# synth.net
KiCad netlist of a schematic drawn in EAGLE
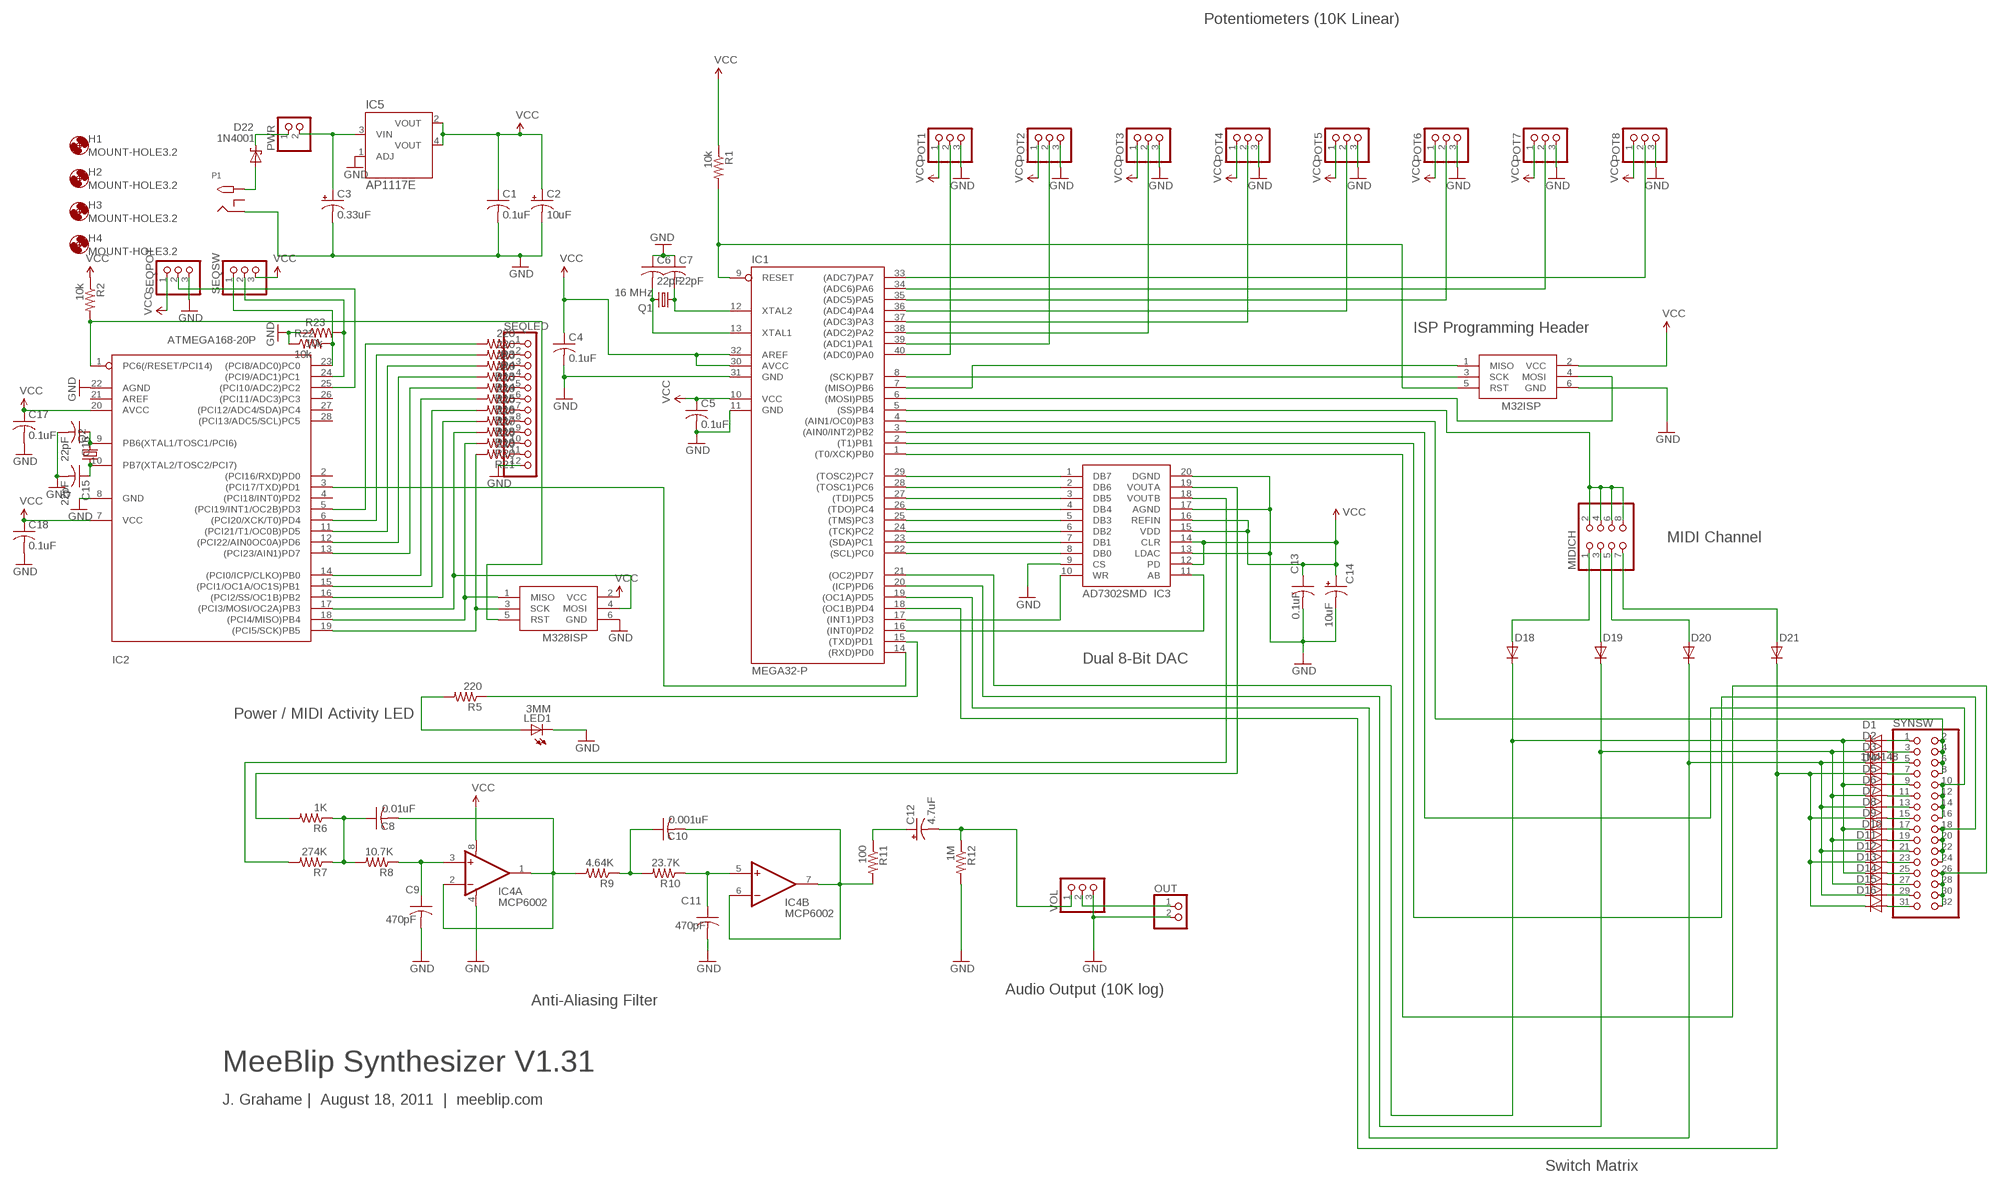
[diagram p0: schematic, sheet 1]

(export (version "E")
  (design (tool "Eeschema 10.0.6"))
  (components
    (comp (ref "C1")
      (value "0.1uF")
      (footprint "eagle-import:C0805K")
      (libsource (lib "eagle-import") (part "C-USC0805K"))
    )
    (comp (ref "C2")
      (value "10uF")
      (footprint "eagle-import:E2-5")
      (libsource (lib "eagle-import") (part "CPOL-USE2-5"))
    )
    (comp (ref "C3")
      (value "0.33uF")
      (footprint "eagle-import:E2-5")
      (libsource (lib "eagle-import") (part "CPOL-USE2-5"))
    )
    (comp (ref "C4")
      (value "0.1uF")
      (footprint "eagle-import:C0805K")
      (libsource (lib "eagle-import") (part "C-USC0805K"))
    )
    (comp (ref "C5")
      (value "0.1uF")
      (footprint "eagle-import:C0805K")
      (libsource (lib "eagle-import") (part "C-USC0805K"))
    )
    (comp (ref "C6")
      (value "22pF")
      (footprint "eagle-import:C0805K")
      (libsource (lib "eagle-import") (part "C-USC0805K"))
    )
    (comp (ref "C7")
      (value "22pF")
      (footprint "eagle-import:C0805K")
      (libsource (lib "eagle-import") (part "C-USC0805K"))
    )
    (comp (ref "C8")
      (value "0.01uF")
      (footprint "eagle-import:C0805K")
      (libsource (lib "eagle-import") (part "C-USC0805K"))
    )
    (comp (ref "C9")
      (value "470pF")
      (footprint "eagle-import:C0805K")
      (libsource (lib "eagle-import") (part "C-USC0805K"))
    )
    (comp (ref "C10")
      (value "0.001uF")
      (footprint "eagle-import:C0805K")
      (libsource (lib "eagle-import") (part "C-USC0805K"))
    )
    (comp (ref "C11")
      (value "470pF")
      (footprint "eagle-import:C0805K")
      (libsource (lib "eagle-import") (part "C-USC0805K"))
    )
    (comp (ref "C12")
      (value "4.7uF")
      (footprint "eagle-import:E2-5")
      (libsource (lib "eagle-import") (part "CPOL-USE2-5"))
    )
    (comp (ref "C13")
      (value "0.1uF")
      (footprint "eagle-import:C0805K")
      (libsource (lib "eagle-import") (part "C-USC0805K"))
    )
    (comp (ref "C14")
      (value "10uF")
      (footprint "eagle-import:E2-5")
      (libsource (lib "eagle-import") (part "CPOL-USE2-5"))
    )
    (comp (ref "C15")
      (value "22pF")
      (footprint "eagle-import:C0805K")
      (libsource (lib "eagle-import") (part "C-USC0805K"))
    )
    (comp (ref "C16")
      (value "22pF")
      (footprint "eagle-import:C0805K")
      (libsource (lib "eagle-import") (part "C-USC0805K"))
    )
    (comp (ref "C17")
      (value "0.1uF")
      (footprint "eagle-import:C0805K")
      (libsource (lib "eagle-import") (part "C-USC0805K"))
    )
    (comp (ref "C18")
      (value "0.1uF")
      (footprint "eagle-import:C0805K")
      (libsource (lib "eagle-import") (part "C-USC0805K"))
    )
    (comp (ref "D1")
      (value "1N4148")
      (footprint "eagle-import:SOD-123")
      (libsource (lib "eagle-import") (part "DIODESOD-123"))
    )
    (comp (ref "D2")
      (value "1N4148")
      (footprint "eagle-import:SOD-123")
      (libsource (lib "eagle-import") (part "DIODESOD-123"))
    )
    (comp (ref "D3")
      (value "1N4148")
      (footprint "eagle-import:SOD-123")
      (libsource (lib "eagle-import") (part "DIODESOD-123"))
    )
    (comp (ref "D4")
      (value "1N4148")
      (footprint "eagle-import:SOD-123")
      (libsource (lib "eagle-import") (part "DIODESOD-123"))
    )
    (comp (ref "D5")
      (value "1N4148")
      (footprint "eagle-import:SOD-123")
      (libsource (lib "eagle-import") (part "DIODESOD-123"))
    )
    (comp (ref "D6")
      (value "1N4148")
      (footprint "eagle-import:SOD-123")
      (libsource (lib "eagle-import") (part "DIODESOD-123"))
    )
    (comp (ref "D7")
      (value "1N4148")
      (footprint "eagle-import:SOD-123")
      (libsource (lib "eagle-import") (part "DIODESOD-123"))
    )
    (comp (ref "D8")
      (value "1N4148")
      (footprint "eagle-import:SOD-123")
      (libsource (lib "eagle-import") (part "DIODESOD-123"))
    )
    (comp (ref "D9")
      (value "1N4148")
      (footprint "eagle-import:SOD-123")
      (libsource (lib "eagle-import") (part "DIODESOD-123"))
    )
    (comp (ref "D10")
      (value "1N4148")
      (footprint "eagle-import:SOD-123")
      (libsource (lib "eagle-import") (part "DIODESOD-123"))
    )
    (comp (ref "D11")
      (value "1N4148")
      (footprint "eagle-import:SOD-123")
      (libsource (lib "eagle-import") (part "DIODESOD-123"))
    )
    (comp (ref "D12")
      (value "1N4148")
      (footprint "eagle-import:SOD-123")
      (libsource (lib "eagle-import") (part "DIODESOD-123"))
    )
    (comp (ref "D13")
      (value "1N4148")
      (footprint "eagle-import:SOD-123")
      (libsource (lib "eagle-import") (part "DIODESOD-123"))
    )
    (comp (ref "D14")
      (value "1N4148")
      (footprint "eagle-import:SOD-123")
      (libsource (lib "eagle-import") (part "DIODESOD-123"))
    )
    (comp (ref "D15")
      (value "1N4148")
      (footprint "eagle-import:SOD-123")
      (libsource (lib "eagle-import") (part "DIODESOD-123"))
    )
    (comp (ref "D16")
      (value "1N4148")
      (footprint "eagle-import:SOD-123")
      (libsource (lib "eagle-import") (part "DIODESOD-123"))
    )
    (comp (ref "D18")
      (value "1N4148")
      (footprint "eagle-import:SOD-123")
      (libsource (lib "eagle-import") (part "DIODESOD-123"))
    )
    (comp (ref "D19")
      (value "1N4148")
      (footprint "eagle-import:SOD-123")
      (libsource (lib "eagle-import") (part "DIODESOD-123"))
    )
    (comp (ref "D20")
      (value "1N4148")
      (footprint "eagle-import:SOD-123")
      (libsource (lib "eagle-import") (part "DIODESOD-123"))
    )
    (comp (ref "D21")
      (value "1N4148")
      (footprint "eagle-import:SOD-123")
      (libsource (lib "eagle-import") (part "DIODESOD-123"))
    )
    (comp (ref "D22")
      (value "1N4001")
      (footprint "eagle-import:DO41-7")
      (libsource (lib "eagle-import") (part "SCHOTTKY-DIODEDO41-7"))
    )
    (comp (ref "H1")
      (value "MOUNT-HOLE3.2")
      (footprint "eagle-import:3,2")
      (libsource (lib "eagle-import") (part "MOUNT-HOLE3.2"))
    )
    (comp (ref "H2")
      (value "MOUNT-HOLE3.2")
      (footprint "eagle-import:3,2")
      (libsource (lib "eagle-import") (part "MOUNT-HOLE3.2"))
    )
    (comp (ref "H3")
      (value "MOUNT-HOLE3.2")
      (footprint "eagle-import:3,2")
      (libsource (lib "eagle-import") (part "MOUNT-HOLE3.2"))
    )
    (comp (ref "H4")
      (value "MOUNT-HOLE3.2")
      (footprint "eagle-import:3,2")
      (libsource (lib "eagle-import") (part "MOUNT-HOLE3.2"))
    )
    (comp (ref "IC1")
      (value "MEGA32-P")
      (footprint "eagle-import:DIL40")
      (libsource (lib "eagle-import") (part "MEGA32-P"))
    )
    (comp (ref "IC2")
      (value "ATMEGA168-20P")
      (footprint "eagle-import:DIL28-3")
      (libsource (lib "eagle-import") (part "ATMEGA168P-20"))
    )
    (comp (ref "IC3")
      (value "AD7302SMD")
      (footprint "eagle-import:TSSOP20")
      (libsource (lib "eagle-import") (part "AD7302SMD"))
    )
    (comp (ref "IC4")
      (value "MCP6002")
      (footprint "eagle-import:DIL08")
      (libsource (lib "eagle-import") (part "MCP6002"))
    )
    (comp (ref "IC5")
      (value "AP1117E")
      (footprint "eagle-import:SOT223-3")
      (libsource (lib "eagle-import") (part "AP1117E"))
    )
    (comp (ref "LED1")
      (value "3MM")
      (footprint "eagle-import:LED3MM")
      (libsource (lib "eagle-import") (part "LED3MM"))
    )
    (comp (ref "M32ISP")
      (value "AVRISP-6")
      (footprint "eagle-import:AVRISP")
      (libsource (lib "eagle-import") (part "AVRISP-6"))
    )
    (comp (ref "M328ISP")
      (value "AVRISP-6")
      (footprint "eagle-import:AVRISP")
      (libsource (lib "eagle-import") (part "AVRISP-6"))
    )
    (comp (ref "MIDICH")
      (value "PINHD-2X4")
      (footprint "eagle-import:2X04")
      (libsource (lib "eagle-import") (part "PINHD-2X4"))
    )
    (comp (ref "OUT")
      (value "PINHD-1X2")
      (footprint "eagle-import:1X02")
      (libsource (lib "eagle-import") (part "PINHD-1X2"))
    )
    (comp (ref "P1")
      (value "2.1MMJACKTHM")
      (footprint "eagle-import:PJ-102A")
      (libsource (lib "eagle-import") (part "2.1MMJACKTHM"))
    )
    (comp (ref "POT1")
      (value "PINHD-1X3")
      (footprint "eagle-import:1X03")
      (libsource (lib "eagle-import") (part "PINHD-1X3"))
    )
    (comp (ref "POT2")
      (value "PINHD-1X3")
      (footprint "eagle-import:1X03")
      (libsource (lib "eagle-import") (part "PINHD-1X3"))
    )
    (comp (ref "POT3")
      (value "PINHD-1X3")
      (footprint "eagle-import:1X03")
      (libsource (lib "eagle-import") (part "PINHD-1X3"))
    )
    (comp (ref "POT4")
      (value "PINHD-1X3")
      (footprint "eagle-import:1X03")
      (libsource (lib "eagle-import") (part "PINHD-1X3"))
    )
    (comp (ref "POT5")
      (value "PINHD-1X3")
      (footprint "eagle-import:1X03")
      (libsource (lib "eagle-import") (part "PINHD-1X3"))
    )
    (comp (ref "POT6")
      (value "PINHD-1X3")
      (footprint "eagle-import:1X03")
      (libsource (lib "eagle-import") (part "PINHD-1X3"))
    )
    (comp (ref "POT7")
      (value "PINHD-1X3")
      (footprint "eagle-import:1X03")
      (libsource (lib "eagle-import") (part "PINHD-1X3"))
    )
    (comp (ref "POT8")
      (value "PINHD-1X3")
      (footprint "eagle-import:1X03")
      (libsource (lib "eagle-import") (part "PINHD-1X3"))
    )
    (comp (ref "PWR")
      (value "PINHD-1X2")
      (footprint "eagle-import:1X02")
      (libsource (lib "eagle-import") (part "PINHD-1X2"))
    )
    (comp (ref "Q1")
      (value "16 MHz")
      (footprint "eagle-import:HC49U-V")
      (libsource (lib "eagle-import") (part "CRYSTALHC49U-V"))
    )
    (comp (ref "Q2")
      (value "CRYSTALHC49U-V")
      (footprint "eagle-import:HC49U-V")
      (libsource (lib "eagle-import") (part "CRYSTALHC49U-V"))
    )
    (comp (ref "R1")
      (value "10k")
      (footprint "eagle-import:R0805")
      (libsource (lib "eagle-import") (part "R-US_R0805"))
    )
    (comp (ref "R2")
      (value "10k")
      (footprint "eagle-import:R0805")
      (libsource (lib "eagle-import") (part "R-US_R0805"))
    )
    (comp (ref "R3")
      (value "220")
      (footprint "eagle-import:R0805")
      (libsource (lib "eagle-import") (part "R-US_R0805"))
    )
    (comp (ref "R4")
      (value "220")
      (footprint "eagle-import:R0805")
      (libsource (lib "eagle-import") (part "R-US_R0805"))
    )
    (comp (ref "R5")
      (value "220")
      (footprint "eagle-import:R0805")
      (libsource (lib "eagle-import") (part "R-US_R0805"))
    )
    (comp (ref "R6")
      (value "1K")
      (footprint "eagle-import:R0805")
      (libsource (lib "eagle-import") (part "R-US_R0805"))
    )
    (comp (ref "R7")
      (value "274K")
      (footprint "eagle-import:R0805")
      (libsource (lib "eagle-import") (part "R-US_R0805"))
    )
    (comp (ref "R8")
      (value "10.7K")
      (footprint "eagle-import:R0805")
      (libsource (lib "eagle-import") (part "R-US_R0805"))
    )
    (comp (ref "R9")
      (value "4.64K")
      (footprint "eagle-import:R0805")
      (libsource (lib "eagle-import") (part "R-US_R0805"))
    )
    (comp (ref "R10")
      (value "23.7K")
      (footprint "eagle-import:R0805")
      (libsource (lib "eagle-import") (part "R-US_R0805"))
    )
    (comp (ref "R11")
      (value "100")
      (footprint "eagle-import:R0805")
      (libsource (lib "eagle-import") (part "R-US_R0805"))
    )
    (comp (ref "R12")
      (value "1M")
      (footprint "eagle-import:R0805")
      (libsource (lib "eagle-import") (part "R-US_R0805"))
    )
    (comp (ref "R13")
      (value "220")
      (footprint "eagle-import:R0805")
      (libsource (lib "eagle-import") (part "R-US_R0805"))
    )
    (comp (ref "R14")
      (value "220")
      (footprint "eagle-import:R0805")
      (libsource (lib "eagle-import") (part "R-US_R0805"))
    )
    (comp (ref "R15")
      (value "220")
      (footprint "eagle-import:R0805")
      (libsource (lib "eagle-import") (part "R-US_R0805"))
    )
    (comp (ref "R16")
      (value "220")
      (footprint "eagle-import:R0805")
      (libsource (lib "eagle-import") (part "R-US_R0805"))
    )
    (comp (ref "R17")
      (value "220")
      (footprint "eagle-import:R0805")
      (libsource (lib "eagle-import") (part "R-US_R0805"))
    )
    (comp (ref "R18")
      (value "220")
      (footprint "eagle-import:R0805")
      (libsource (lib "eagle-import") (part "R-US_R0805"))
    )
    (comp (ref "R19")
      (value "220")
      (footprint "eagle-import:R0805")
      (libsource (lib "eagle-import") (part "R-US_R0805"))
    )
    (comp (ref "R20")
      (value "220")
      (footprint "eagle-import:R0805")
      (libsource (lib "eagle-import") (part "R-US_R0805"))
    )
    (comp (ref "R21")
      (value "220")
      (footprint "eagle-import:R0805")
      (libsource (lib "eagle-import") (part "R-US_R0805"))
    )
    (comp (ref "R22")
      (value "10k")
      (footprint "eagle-import:R0805")
      (libsource (lib "eagle-import") (part "R-US_R0805"))
    )
    (comp (ref "R23")
      (value "10k")
      (footprint "eagle-import:R0805")
      (libsource (lib "eagle-import") (part "R-US_R0805"))
    )
    (comp (ref "SEQLED")
      (value "PINHD-1X12")
      (footprint "eagle-import:1X12")
      (libsource (lib "eagle-import") (part "PINHD-1X12"))
    )
    (comp (ref "SEQPOT")
      (value "PINHD-1X3")
      (footprint "eagle-import:1X03")
      (libsource (lib "eagle-import") (part "PINHD-1X3"))
    )
    (comp (ref "SEQSW")
      (value "PINHD-1X3")
      (footprint "eagle-import:1X03")
      (libsource (lib "eagle-import") (part "PINHD-1X3"))
    )
    (comp (ref "SYNSW")
      (value "PINHD-2X16")
      (footprint "eagle-import:2X16")
      (libsource (lib "eagle-import") (part "PINHD-2X16"))
    )
    (comp (ref "VOL")
      (value "PINHD-1X3")
      (footprint "eagle-import:1X03")
      (libsource (lib "eagle-import") (part "PINHD-1X3"))
    )
  )
  (nets
    (net (code "1") (name "GND") (class "Default")
      (node (ref "C1") (pin "2") (pinfunction "2_2") (pintype "passive"))
      (node (ref "C11") (pin "2") (pinfunction "2_2") (pintype "passive"))
      (node (ref "C13") (pin "2") (pinfunction "2_2") (pintype "passive"))
      (node (ref "C14") (pin "-") (pinfunction "-_-") (pintype "passive"))
      (node (ref "C15") (pin "2") (pinfunction "2_2") (pintype "passive"))
      (node (ref "C16") (pin "2") (pinfunction "2_2") (pintype "passive"))
      (node (ref "C17") (pin "2") (pinfunction "2_2") (pintype "passive"))
      (node (ref "C18") (pin "2") (pinfunction "2_2") (pintype "passive"))
      (node (ref "C2") (pin "-") (pinfunction "-_-") (pintype "passive"))
      (node (ref "C3") (pin "-") (pinfunction "-_-") (pintype "passive"))
      (node (ref "C4") (pin "2") (pinfunction "2_2") (pintype "passive"))
      (node (ref "C5") (pin "2") (pinfunction "2_2") (pintype "passive"))
      (node (ref "C6") (pin "1") (pinfunction "1_1") (pintype "passive"))
      (node (ref "C7") (pin "1") (pinfunction "1_1") (pintype "passive"))
      (node (ref "C9") (pin "2") (pinfunction "2_2") (pintype "passive"))
      (node (ref "IC1") (pin "11") (pinfunction "GND_11") (pintype "power_in"))
      (node (ref "IC1") (pin "31") (pinfunction "GND_31") (pintype "power_in"))
      (node (ref "IC2") (pin "22") (pinfunction "AGND_22") (pintype "bidirectional"))
      (node (ref "IC2") (pin "8") (pinfunction "GND_8") (pintype "bidirectional"))
      (node (ref "IC3") (pin "13") (pinfunction "LDAC_13") (pintype "bidirectional"))
      (node (ref "IC3") (pin "17") (pinfunction "AGND_17") (pintype "bidirectional"))
      (node (ref "IC3") (pin "20") (pinfunction "DGND_20") (pintype "bidirectional"))
      (node (ref "IC3") (pin "9") (pinfunction "CS_9") (pintype "bidirectional"))
      (node (ref "IC4") (pin "4") (pinfunction "V-_4") (pintype "power_in"))
      (node (ref "IC5") (pin "1") (pinfunction "ADJ_1") (pintype "bidirectional"))
      (node (ref "LED1") (pin "K") (pinfunction "C_K") (pintype "passive"))
      (node (ref "M328ISP") (pin "6") (pinfunction "GND_6") (pintype "power_in"))
      (node (ref "M32ISP") (pin "6") (pinfunction "GND_6") (pintype "power_in"))
      (node (ref "OUT") (pin "2") (pinfunction "2_2") (pintype "passive"))
      (node (ref "P1") (pin "RING") (pinfunction "RING_RING") (pintype "bidirectional"))
      (node (ref "POT1") (pin "3") (pinfunction "3_3") (pintype "passive"))
      (node (ref "POT2") (pin "3") (pinfunction "3_3") (pintype "passive"))
      (node (ref "POT3") (pin "3") (pinfunction "3_3") (pintype "passive"))
      (node (ref "POT4") (pin "3") (pinfunction "3_3") (pintype "passive"))
      (node (ref "POT5") (pin "3") (pinfunction "3_3") (pintype "passive"))
      (node (ref "POT6") (pin "3") (pinfunction "3_3") (pintype "passive"))
      (node (ref "POT7") (pin "3") (pinfunction "3_3") (pintype "passive"))
      (node (ref "POT8") (pin "3") (pinfunction "3_3") (pintype "passive"))
      (node (ref "R12") (pin "2") (pinfunction "2_2") (pintype "passive"))
      (node (ref "R22") (pin "1") (pinfunction "1_1") (pintype "passive"))
      (node (ref "R23") (pin "1") (pinfunction "1_1") (pintype "passive"))
      (node (ref "SEQLED") (pin "12") (pinfunction "12_12") (pintype "passive"))
      (node (ref "SEQPOT") (pin "3") (pinfunction "3_3") (pintype "passive"))
      (node (ref "VOL") (pin "3") (pinfunction "3_3") (pintype "passive"))
    )
    (net (code "2") (name "Net-(C8-Pad1)") (class "Default")
      (node (ref "C8") (pin "1") (pinfunction "1_1") (pintype "passive"))
      (node (ref "R6") (pin "1") (pinfunction "1_1") (pintype "passive"))
      (node (ref "R7") (pin "1") (pinfunction "1_1") (pintype "passive"))
      (node (ref "R8") (pin "2") (pinfunction "2_2") (pintype "passive"))
    )
    (net (code "3") (name "Net-(C10-Pad1)") (class "Default")
      (node (ref "C10") (pin "1") (pinfunction "1_1") (pintype "passive"))
      (node (ref "R10") (pin "2") (pinfunction "2_2") (pintype "passive"))
      (node (ref "R9") (pin "1") (pinfunction "1_1") (pintype "passive"))
    )
    (net (code "4") (name "Net-(C12-Pad+)") (class "Default")
      (node (ref "C12") (pin "+") (pinfunction "+_+") (pintype "passive"))
      (node (ref "R11") (pin "1") (pinfunction "1_1") (pintype "passive"))
    )
    (net (code "5") (name "Net-(C12-Pad-)") (class "Default")
      (node (ref "C12") (pin "-") (pinfunction "-_-") (pintype "passive"))
      (node (ref "R12") (pin "1") (pinfunction "1_1") (pintype "passive"))
      (node (ref "VOL") (pin "1") (pinfunction "1_1") (pintype "passive"))
    )
    (net (code "6") (name "Net-(D1-PadA)") (class "Default")
      (node (ref "D1") (pin "A") (pinfunction "A_A") (pintype "passive"))
      (node (ref "SYNSW") (pin "1") (pinfunction "1_1") (pintype "passive"))
    )
    (net (code "7") (name "Net-(D2-PadA)") (class "Default")
      (node (ref "D2") (pin "A") (pinfunction "A_A") (pintype "passive"))
      (node (ref "SYNSW") (pin "3") (pinfunction "3_3") (pintype "passive"))
    )
    (net (code "8") (name "Net-(D3-PadA)") (class "Default")
      (node (ref "D3") (pin "A") (pinfunction "A_A") (pintype "passive"))
      (node (ref "SYNSW") (pin "5") (pinfunction "5_5") (pintype "passive"))
    )
    (net (code "9") (name "Net-(D4-PadA)") (class "Default")
      (node (ref "D4") (pin "A") (pinfunction "A_A") (pintype "passive"))
      (node (ref "SYNSW") (pin "7") (pinfunction "7_7") (pintype "passive"))
    )
    (net (code "10") (name "Net-(D5-PadA)") (class "Default")
      (node (ref "D5") (pin "A") (pinfunction "A_A") (pintype "passive"))
      (node (ref "SYNSW") (pin "9") (pinfunction "9_9") (pintype "passive"))
    )
    (net (code "11") (name "Net-(D6-PadA)") (class "Default")
      (node (ref "D6") (pin "A") (pinfunction "A_A") (pintype "passive"))
      (node (ref "SYNSW") (pin "11") (pinfunction "11_11") (pintype "passive"))
    )
    (net (code "12") (name "Net-(D7-PadA)") (class "Default")
      (node (ref "D7") (pin "A") (pinfunction "A_A") (pintype "passive"))
      (node (ref "SYNSW") (pin "13") (pinfunction "13_13") (pintype "passive"))
    )
    (net (code "13") (name "Net-(D8-PadA)") (class "Default")
      (node (ref "D8") (pin "A") (pinfunction "A_A") (pintype "passive"))
      (node (ref "SYNSW") (pin "15") (pinfunction "15_15") (pintype "passive"))
    )
    (net (code "14") (name "Net-(D9-PadA)") (class "Default")
      (node (ref "D9") (pin "A") (pinfunction "A_A") (pintype "passive"))
      (node (ref "SYNSW") (pin "17") (pinfunction "17_17") (pintype "passive"))
    )
    (net (code "15") (name "Net-(D10-PadA)") (class "Default")
      (node (ref "D10") (pin "A") (pinfunction "A_A") (pintype "passive"))
      (node (ref "SYNSW") (pin "19") (pinfunction "19_19") (pintype "passive"))
    )
    (net (code "16") (name "Net-(D11-PadA)") (class "Default")
      (node (ref "D11") (pin "A") (pinfunction "A_A") (pintype "passive"))
      (node (ref "SYNSW") (pin "21") (pinfunction "21_21") (pintype "passive"))
    )
    (net (code "17") (name "Net-(D12-PadA)") (class "Default")
      (node (ref "D12") (pin "A") (pinfunction "A_A") (pintype "passive"))
      (node (ref "SYNSW") (pin "23") (pinfunction "23_23") (pintype "passive"))
    )
    (net (code "18") (name "Net-(D13-PadA)") (class "Default")
      (node (ref "D13") (pin "A") (pinfunction "A_A") (pintype "passive"))
      (node (ref "SYNSW") (pin "25") (pinfunction "25_25") (pintype "passive"))
    )
    (net (code "19") (name "Net-(D14-PadA)") (class "Default")
      (node (ref "D14") (pin "A") (pinfunction "A_A") (pintype "passive"))
      (node (ref "SYNSW") (pin "27") (pinfunction "27_27") (pintype "passive"))
    )
    (net (code "20") (name "Net-(D15-PadA)") (class "Default")
      (node (ref "D15") (pin "A") (pinfunction "A_A") (pintype "passive"))
      (node (ref "SYNSW") (pin "29") (pinfunction "29_29") (pintype "passive"))
    )
    (net (code "21") (name "Net-(D16-PadA)") (class "Default")
      (node (ref "D16") (pin "A") (pinfunction "A_A") (pintype "passive"))
      (node (ref "SYNSW") (pin "31") (pinfunction "31_31") (pintype "passive"))
    )
    (net (code "22") (name "Net-(D18-PadA)") (class "Default")
      (node (ref "D18") (pin "A") (pinfunction "A_A") (pintype "passive"))
      (node (ref "MIDICH") (pin "1") (pinfunction "1_1") (pintype "passive"))
    )
    (net (code "23") (name "Net-(D19-PadA)") (class "Default")
      (node (ref "D19") (pin "A") (pinfunction "A_A") (pintype "passive"))
      (node (ref "MIDICH") (pin "3") (pinfunction "3_3") (pintype "passive"))
    )
    (net (code "24") (name "Net-(D20-PadA)") (class "Default")
      (node (ref "D20") (pin "A") (pinfunction "A_A") (pintype "passive"))
      (node (ref "MIDICH") (pin "5") (pinfunction "5_5") (pintype "passive"))
    )
    (net (code "25") (name "Net-(D21-PadA)") (class "Default")
      (node (ref "D21") (pin "A") (pinfunction "A_A") (pintype "passive"))
      (node (ref "MIDICH") (pin "7") (pinfunction "7_7") (pintype "passive"))
    )
    (net (code "26") (name "Net-(D22-PadA)") (class "Default")
      (node (ref "D22") (pin "A") (pinfunction "A_A") (pintype "passive"))
      (node (ref "P1") (pin "TIP") (pinfunction "TIP_TIP") (pintype "bidirectional"))
    )
    (net (code "27") (name "Net-(D22-PadC)") (class "Default")
      (node (ref "D22") (pin "C") (pinfunction "C_C") (pintype "passive"))
      (node (ref "PWR") (pin "1") (pinfunction "1_1") (pintype "passive"))
    )
    (net (code "28") (name "Net-(IC1-(ADC0)PA0)") (class "Default")
      (node (ref "IC1") (pin "40") (pinfunction "(ADC0)PA0_40") (pintype "bidirectional"))
      (node (ref "POT1") (pin "2") (pinfunction "2_2") (pintype "passive"))
    )
    (net (code "29") (name "Net-(IC1-(ADC1)PA1)") (class "Default")
      (node (ref "IC1") (pin "39") (pinfunction "(ADC1)PA1_39") (pintype "bidirectional"))
      (node (ref "POT2") (pin "2") (pinfunction "2_2") (pintype "passive"))
    )
    (net (code "30") (name "Net-(IC1-(ADC2)PA2)") (class "Default")
      (node (ref "IC1") (pin "38") (pinfunction "(ADC2)PA2_38") (pintype "bidirectional"))
      (node (ref "POT3") (pin "2") (pinfunction "2_2") (pintype "passive"))
    )
    (net (code "31") (name "Net-(IC1-(ADC3)PA3)") (class "Default")
      (node (ref "IC1") (pin "37") (pinfunction "(ADC3)PA3_37") (pintype "bidirectional"))
      (node (ref "POT4") (pin "2") (pinfunction "2_2") (pintype "passive"))
    )
    (net (code "32") (name "Net-(IC1-(ADC4)PA4)") (class "Default")
      (node (ref "IC1") (pin "36") (pinfunction "(ADC4)PA4_36") (pintype "bidirectional"))
      (node (ref "POT5") (pin "2") (pinfunction "2_2") (pintype "passive"))
    )
    (net (code "33") (name "Net-(IC1-(ADC5)PA5)") (class "Default")
      (node (ref "IC1") (pin "35") (pinfunction "(ADC5)PA5_35") (pintype "bidirectional"))
      (node (ref "POT6") (pin "2") (pinfunction "2_2") (pintype "passive"))
    )
    (net (code "34") (name "Net-(IC1-(ADC6)PA6)") (class "Default")
      (node (ref "IC1") (pin "34") (pinfunction "(ADC6)PA6_34") (pintype "bidirectional"))
      (node (ref "POT7") (pin "2") (pinfunction "2_2") (pintype "passive"))
    )
    (net (code "35") (name "Net-(IC1-(ADC7)PA7)") (class "Default")
      (node (ref "IC1") (pin "33") (pinfunction "(ADC7)PA7_33") (pintype "bidirectional"))
      (node (ref "POT8") (pin "2") (pinfunction "2_2") (pintype "passive"))
    )
    (net (code "36") (name "Net-(IC1-(AIN0{slash}INT2)PB2)") (class "Default")
      (node (ref "IC1") (pin "3") (pinfunction "(AIN0/INT2)PB2_3") (pintype "bidirectional"))
      (node (ref "SYNSW") (pin "10") (pinfunction "10_10") (pintype "passive"))
      (node (ref "SYNSW") (pin "12") (pinfunction "12_12") (pintype "passive"))
      (node (ref "SYNSW") (pin "14") (pinfunction "14_14") (pintype "passive"))
      (node (ref "SYNSW") (pin "16") (pinfunction "16_16") (pintype "passive"))
    )
    (net (code "37") (name "Net-(IC1-(AIN1{slash}OC0)PB3)") (class "Default")
      (node (ref "IC1") (pin "4") (pinfunction "(AIN1/OC0)PB3_4") (pintype "bidirectional"))
      (node (ref "SYNSW") (pin "2") (pinfunction "2_2") (pintype "passive"))
      (node (ref "SYNSW") (pin "4") (pinfunction "4_4") (pintype "passive"))
      (node (ref "SYNSW") (pin "6") (pinfunction "6_6") (pintype "passive"))
      (node (ref "SYNSW") (pin "8") (pinfunction "8_8") (pintype "passive"))
    )
    (net (code "38") (name "Net-(IC1-(ICP)PD6)") (class "Default")
      (node (ref "D10") (pin "C") (pinfunction "C_C") (pintype "passive"))
      (node (ref "D14") (pin "C") (pinfunction "C_C") (pintype "passive"))
      (node (ref "D19") (pin "C") (pinfunction "C_C") (pintype "passive"))
      (node (ref "D2") (pin "C") (pinfunction "C_C") (pintype "passive"))
      (node (ref "D6") (pin "C") (pinfunction "C_C") (pintype "passive"))
      (node (ref "IC1") (pin "20") (pinfunction "(ICP)PD6_20") (pintype "bidirectional"))
    )
    (net (code "39") (name "Net-(IC1-(INT0)PD2)") (class "Default")
      (node (ref "IC1") (pin "16") (pinfunction "(INT0)PD2_16") (pintype "bidirectional"))
      (node (ref "IC3") (pin "11") (pinfunction "AB_11") (pintype "bidirectional"))
    )
    (net (code "40") (name "Net-(IC1-(INT1)PD3)") (class "Default")
      (node (ref "IC1") (pin "17") (pinfunction "(INT1)PD3_17") (pintype "bidirectional"))
      (node (ref "IC3") (pin "10") (pinfunction "WR_10") (pintype "bidirectional"))
    )
    (net (code "41") (name "Net-(IC1-(MISO)PB6)") (class "Default")
      (node (ref "IC1") (pin "7") (pinfunction "(MISO)PB6_7") (pintype "bidirectional"))
      (node (ref "M32ISP") (pin "1") (pinfunction "MISO_1") (pintype "input"))
    )
    (net (code "42") (name "Net-(IC1-(MOSI)PB5)") (class "Default")
      (node (ref "IC1") (pin "6") (pinfunction "(MOSI)PB5_6") (pintype "bidirectional"))
      (node (ref "M32ISP") (pin "4") (pinfunction "MOSI_4") (pintype "output"))
    )
    (net (code "43") (name "Net-(IC1-(OC1A)PD5)") (class "Default")
      (node (ref "D11") (pin "C") (pinfunction "C_C") (pintype "passive"))
      (node (ref "D15") (pin "C") (pinfunction "C_C") (pintype "passive"))
      (node (ref "D20") (pin "C") (pinfunction "C_C") (pintype "passive"))
      (node (ref "D3") (pin "C") (pinfunction "C_C") (pintype "passive"))
      (node (ref "D7") (pin "C") (pinfunction "C_C") (pintype "passive"))
      (node (ref "IC1") (pin "19") (pinfunction "(OC1A)PD5_19") (pintype "bidirectional"))
    )
    (net (code "44") (name "Net-(IC1-(OC1B)PD4)") (class "Default")
      (node (ref "D12") (pin "C") (pinfunction "C_C") (pintype "passive"))
      (node (ref "D16") (pin "C") (pinfunction "C_C") (pintype "passive"))
      (node (ref "D21") (pin "C") (pinfunction "C_C") (pintype "passive"))
      (node (ref "D4") (pin "C") (pinfunction "C_C") (pintype "passive"))
      (node (ref "D8") (pin "C") (pinfunction "C_C") (pintype "passive"))
      (node (ref "IC1") (pin "18") (pinfunction "(OC1B)PD4_18") (pintype "bidirectional"))
    )
    (net (code "45") (name "Net-(IC1-(OC2)PD7)") (class "Default")
      (node (ref "D1") (pin "C") (pinfunction "C_C") (pintype "passive"))
      (node (ref "D13") (pin "C") (pinfunction "C_C") (pintype "passive"))
      (node (ref "D18") (pin "C") (pinfunction "C_C") (pintype "passive"))
      (node (ref "D5") (pin "C") (pinfunction "C_C") (pintype "passive"))
      (node (ref "D9") (pin "C") (pinfunction "C_C") (pintype "passive"))
      (node (ref "IC1") (pin "21") (pinfunction "(OC2)PD7_21") (pintype "bidirectional"))
    )
    (net (code "46") (name "Net-(IC1-(RXD)PD0)") (class "Default")
      (node (ref "IC1") (pin "14") (pinfunction "(RXD)PD0_14") (pintype "bidirectional"))
      (node (ref "IC2") (pin "3") (pinfunction "(PCI17/TXD)PD1_3") (pintype "bidirectional"))
    )
    (net (code "47") (name "Net-(IC1-(SCK)PB7)") (class "Default")
      (node (ref "IC1") (pin "8") (pinfunction "(SCK)PB7_8") (pintype "bidirectional"))
      (node (ref "M32ISP") (pin "3") (pinfunction "SCK_3") (pintype "output"))
    )
    (net (code "48") (name "Net-(IC1-(SCL)PC0)") (class "Default")
      (node (ref "IC1") (pin "22") (pinfunction "(SCL)PC0_22") (pintype "bidirectional"))
      (node (ref "IC3") (pin "8") (pinfunction "DB0_8") (pintype "bidirectional"))
    )
    (net (code "49") (name "Net-(IC1-(SDA)PC1)") (class "Default")
      (node (ref "IC1") (pin "23") (pinfunction "(SDA)PC1_23") (pintype "bidirectional"))
      (node (ref "IC3") (pin "7") (pinfunction "DB1_7") (pintype "bidirectional"))
    )
    (net (code "50") (name "Net-(IC1-(SS)PB4)") (class "Default")
      (node (ref "IC1") (pin "5") (pinfunction "(SS)PB4_5") (pintype "bidirectional"))
      (node (ref "MIDICH") (pin "2") (pinfunction "2_2") (pintype "passive"))
      (node (ref "MIDICH") (pin "4") (pinfunction "4_4") (pintype "passive"))
      (node (ref "MIDICH") (pin "6") (pinfunction "6_6") (pintype "passive"))
      (node (ref "MIDICH") (pin "8") (pinfunction "8_8") (pintype "passive"))
    )
    (net (code "51") (name "Net-(IC1-(T0{slash}XCK)PB0)") (class "Default")
      (node (ref "IC1") (pin "1") (pinfunction "(T0/XCK)PB0_1") (pintype "bidirectional"))
      (node (ref "SYNSW") (pin "26") (pinfunction "26_26") (pintype "passive"))
      (node (ref "SYNSW") (pin "28") (pinfunction "28_28") (pintype "passive"))
      (node (ref "SYNSW") (pin "30") (pinfunction "30_30") (pintype "passive"))
      (node (ref "SYNSW") (pin "32") (pinfunction "32_32") (pintype "passive"))
    )
    (net (code "52") (name "Net-(IC1-(T1)PB1)") (class "Default")
      (node (ref "IC1") (pin "2") (pinfunction "(T1)PB1_2") (pintype "bidirectional"))
      (node (ref "SYNSW") (pin "18") (pinfunction "18_18") (pintype "passive"))
      (node (ref "SYNSW") (pin "20") (pinfunction "20_20") (pintype "passive"))
      (node (ref "SYNSW") (pin "22") (pinfunction "22_22") (pintype "passive"))
      (node (ref "SYNSW") (pin "24") (pinfunction "24_24") (pintype "passive"))
    )
    (net (code "53") (name "Net-(IC1-(TCK)PC2)") (class "Default")
      (node (ref "IC1") (pin "24") (pinfunction "(TCK)PC2_24") (pintype "bidirectional"))
      (node (ref "IC3") (pin "6") (pinfunction "DB2_6") (pintype "bidirectional"))
    )
    (net (code "54") (name "Net-(IC1-(TDI)PC5)") (class "Default")
      (node (ref "IC1") (pin "27") (pinfunction "(TDI)PC5_27") (pintype "bidirectional"))
      (node (ref "IC3") (pin "3") (pinfunction "DB5_3") (pintype "bidirectional"))
    )
    (net (code "55") (name "Net-(IC1-(TDO)PC4)") (class "Default")
      (node (ref "IC1") (pin "26") (pinfunction "(TDO)PC4_26") (pintype "bidirectional"))
      (node (ref "IC3") (pin "4") (pinfunction "DB4_4") (pintype "bidirectional"))
    )
    (net (code "56") (name "Net-(IC1-(TMS)PC3)") (class "Default")
      (node (ref "IC1") (pin "25") (pinfunction "(TMS)PC3_25") (pintype "bidirectional"))
      (node (ref "IC3") (pin "5") (pinfunction "DB3_5") (pintype "bidirectional"))
    )
    (net (code "57") (name "Net-(IC1-(TOSC1)PC6)") (class "Default")
      (node (ref "IC1") (pin "28") (pinfunction "(TOSC1)PC6_28") (pintype "bidirectional"))
      (node (ref "IC3") (pin "2") (pinfunction "DB6_2") (pintype "bidirectional"))
    )
    (net (code "58") (name "Net-(IC1-(TOSC2)PC7)") (class "Default")
      (node (ref "IC1") (pin "29") (pinfunction "(TOSC2)PC7_29") (pintype "bidirectional"))
      (node (ref "IC3") (pin "1") (pinfunction "DB7_1") (pintype "bidirectional"))
    )
    (net (code "59") (name "Net-(IC1-(TXD)PD1)") (class "Default")
      (node (ref "IC1") (pin "15") (pinfunction "(TXD)PD1_15") (pintype "bidirectional"))
      (node (ref "R5") (pin "1") (pinfunction "1_1") (pintype "passive"))
    )
    (net (code "60") (name "Net-(IC1-RESET)") (class "Default")
      (node (ref "IC1") (pin "9") (pinfunction "RESET_9") (pintype "input"))
      (node (ref "M32ISP") (pin "5") (pinfunction "RST_5") (pintype "output"))
      (node (ref "R1") (pin "2") (pinfunction "2_2") (pintype "passive"))
    )
    (net (code "61") (name "Net-(IC1-XTAL1)") (class "Default")
      (node (ref "C6") (pin "2") (pinfunction "2_2") (pintype "passive"))
      (node (ref "IC1") (pin "13") (pinfunction "XTAL1_13") (pintype "bidirectional"))
      (node (ref "Q1") (pin "2") (pinfunction "2_2") (pintype "passive"))
    )
    (net (code "62") (name "Net-(IC1-XTAL2)") (class "Default")
      (node (ref "C7") (pin "2") (pinfunction "2_2") (pintype "passive"))
      (node (ref "IC1") (pin "12") (pinfunction "XTAL2_12") (pintype "bidirectional"))
      (node (ref "Q1") (pin "1") (pinfunction "1_1") (pintype "passive"))
    )
    (net (code "63") (name "Net-(IC2-(PCI0{slash}ICP{slash}CLKO)PB0)") (class "Default")
      (node (ref "IC2") (pin "14") (pinfunction "(PCI0/ICP/CLKO)PB0_14") (pintype "bidirectional"))
      (node (ref "R16") (pin "2") (pinfunction "2_2") (pintype "passive"))
    )
    (net (code "64") (name "Net-(IC2-(PCI1{slash}OC1A{slash}OC1S)PB1)") (class "Default")
      (node (ref "IC2") (pin "15") (pinfunction "(PCI1/OC1A/OC1S)PB1_15") (pintype "bidirectional"))
      (node (ref "R17") (pin "2") (pinfunction "2_2") (pintype "passive"))
    )
    (net (code "65") (name "Net-(IC2-(PCI2{slash}SS{slash}OC1B)PB2)") (class "Default")
      (node (ref "IC2") (pin "16") (pinfunction "(PCI2/SS/OC1B)PB2_16") (pintype "bidirectional"))
      (node (ref "R18") (pin "2") (pinfunction "2_2") (pintype "passive"))
    )
    (net (code "66") (name "Net-(IC2-(PCI3{slash}MOSI{slash}OC2A)PB3)") (class "Default")
      (node (ref "IC2") (pin "17") (pinfunction "(PCI3/MOSI/OC2A)PB3_17") (pintype "bidirectional"))
      (node (ref "M328ISP") (pin "4") (pinfunction "MOSI_4") (pintype "output"))
      (node (ref "R19") (pin "2") (pinfunction "2_2") (pintype "passive"))
    )
    (net (code "67") (name "Net-(IC2-(PCI4{slash}MISO)PB4)") (class "Default")
      (node (ref "IC2") (pin "18") (pinfunction "(PCI4/MISO)PB4_18") (pintype "bidirectional"))
      (node (ref "M328ISP") (pin "1") (pinfunction "MISO_1") (pintype "input"))
      (node (ref "R20") (pin "2") (pinfunction "2_2") (pintype "passive"))
    )
    (net (code "68") (name "Net-(IC2-(PCI5{slash}SCK)PB5)") (class "Default")
      (node (ref "IC2") (pin "19") (pinfunction "(PCI5/SCK)PB5_19") (pintype "bidirectional"))
      (node (ref "M328ISP") (pin "3") (pinfunction "SCK_3") (pintype "output"))
      (node (ref "R21") (pin "2") (pinfunction "2_2") (pintype "passive"))
    )
    (net (code "69") (name "Net-(IC2-(PCI8{slash}ADC0)PC0)") (class "Default")
      (node (ref "IC2") (pin "23") (pinfunction "(PCI8/ADC0)PC0_23") (pintype "bidirectional"))
      (node (ref "R22") (pin "2") (pinfunction "2_2") (pintype "passive"))
      (node (ref "SEQSW") (pin "1") (pinfunction "1_1") (pintype "passive"))
    )
    (net (code "70") (name "Net-(IC2-(PCI9{slash}ADC1)PC1)") (class "Default")
      (node (ref "IC2") (pin "24") (pinfunction "(PCI9/ADC1)PC1_24") (pintype "bidirectional"))
      (node (ref "R23") (pin "2") (pinfunction "2_2") (pintype "passive"))
      (node (ref "SEQSW") (pin "2") (pinfunction "2_2") (pintype "passive"))
    )
    (net (code "71") (name "Net-(IC2-(PCI10{slash}ADC2)PC2)") (class "Default")
      (node (ref "IC2") (pin "25") (pinfunction "(PCI10/ADC2)PC2_25") (pintype "bidirectional"))
      (node (ref "SEQPOT") (pin "2") (pinfunction "2_2") (pintype "passive"))
    )
    (net (code "72") (name "Net-(IC2-(PCI19{slash}INT1{slash}OC2B)PD3)") (class "Default")
      (node (ref "IC2") (pin "5") (pinfunction "(PCI19/INT1/OC2B)PD3_5") (pintype "bidirectional"))
      (node (ref "R3") (pin "2") (pinfunction "2_2") (pintype "passive"))
    )
    (net (code "73") (name "Net-(IC2-(PCI20{slash}XCK{slash}T0)PD4)") (class "Default")
      (node (ref "IC2") (pin "6") (pinfunction "(PCI20/XCK/T0)PD4_6") (pintype "bidirectional"))
      (node (ref "R4") (pin "2") (pinfunction "2_2") (pintype "passive"))
    )
    (net (code "74") (name "Net-(IC2-(PCI21{slash}T1{slash}OC0B)PD5)") (class "Default")
      (node (ref "IC2") (pin "11") (pinfunction "(PCI21/T1/OC0B)PD5_11") (pintype "bidirectional"))
      (node (ref "R13") (pin "2") (pinfunction "2_2") (pintype "passive"))
    )
    (net (code "75") (name "Net-(IC2-(PCI22{slash}AIN0OC0A)PD6)") (class "Default")
      (node (ref "IC2") (pin "12") (pinfunction "(PCI22/AIN0OC0A)PD6_12") (pintype "bidirectional"))
      (node (ref "R14") (pin "2") (pinfunction "2_2") (pintype "passive"))
    )
    (net (code "76") (name "Net-(IC2-(PCI23{slash}AIN1)PD7)") (class "Default")
      (node (ref "IC2") (pin "13") (pinfunction "(PCI23/AIN1)PD7_13") (pintype "bidirectional"))
      (node (ref "R15") (pin "2") (pinfunction "2_2") (pintype "passive"))
    )
    (net (code "77") (name "Net-(IC2-PB6(XTAL1{slash}TOSC1{slash}PCI6))") (class "Default")
      (node (ref "C16") (pin "1") (pinfunction "1_1") (pintype "passive"))
      (node (ref "IC2") (pin "9") (pinfunction "PB6(XTAL1/TOSC1/PCI6)_9") (pintype "bidirectional"))
      (node (ref "Q2") (pin "2") (pinfunction "2_2") (pintype "passive"))
    )
    (net (code "78") (name "Net-(IC2-PB7(XTAL2{slash}TOSC2{slash}PCI7))") (class "Default")
      (node (ref "C15") (pin "1") (pinfunction "1_1") (pintype "passive"))
      (node (ref "IC2") (pin "10") (pinfunction "PB7(XTAL2/TOSC2/PCI7)_10") (pintype "bidirectional"))
      (node (ref "Q2") (pin "1") (pinfunction "1_1") (pintype "passive"))
    )
    (net (code "79") (name "Net-(IC2-PC6({slash}RESET{slash}PCI14))") (class "Default")
      (node (ref "IC2") (pin "1") (pinfunction "PC6(/RESET/PCI14)_1") (pintype "bidirectional"))
      (node (ref "M328ISP") (pin "5") (pinfunction "RST_5") (pintype "output"))
      (node (ref "R2") (pin "2") (pinfunction "2_2") (pintype "passive"))
    )
    (net (code "80") (name "Net-(IC3-VOUTA)") (class "Default")
      (node (ref "IC3") (pin "19") (pinfunction "VOUTA_19") (pintype "bidirectional"))
      (node (ref "R6") (pin "2") (pinfunction "2_2") (pintype "passive"))
    )
    (net (code "81") (name "Net-(IC3-VOUTB)") (class "Default")
      (node (ref "IC3") (pin "18") (pinfunction "VOUTB_18") (pintype "bidirectional"))
      (node (ref "R7") (pin "2") (pinfunction "2_2") (pintype "passive"))
    )
    (net (code "82") (name "Net-(IC4A-+IN)") (class "Default")
      (node (ref "C9") (pin "1") (pinfunction "1_1") (pintype "passive"))
      (node (ref "IC4") (pin "3") (pinfunction "+IN_3") (pintype "input"))
      (node (ref "R8") (pin "1") (pinfunction "1_1") (pintype "passive"))
    )
    (net (code "83") (name "Net-(IC4A--IN)") (class "Default")
      (node (ref "C8") (pin "2") (pinfunction "2_2") (pintype "passive"))
      (node (ref "IC4") (pin "1") (pinfunction "OUT_1") (pintype "output"))
      (node (ref "IC4") (pin "2") (pinfunction "-IN_2") (pintype "input"))
      (node (ref "R9") (pin "2") (pinfunction "2_2") (pintype "passive"))
    )
    (net (code "84") (name "Net-(IC4B-+IN)") (class "Default")
      (node (ref "C11") (pin "1") (pinfunction "1_1") (pintype "passive"))
      (node (ref "IC4") (pin "5") (pinfunction "+IN_5") (pintype "input"))
      (node (ref "R10") (pin "1") (pinfunction "1_1") (pintype "passive"))
    )
    (net (code "85") (name "Net-(IC4B--IN)") (class "Default")
      (node (ref "C10") (pin "2") (pinfunction "2_2") (pintype "passive"))
      (node (ref "IC4") (pin "6") (pinfunction "-IN_6") (pintype "input"))
      (node (ref "IC4") (pin "7") (pinfunction "OUT_7") (pintype "output"))
      (node (ref "R11") (pin "2") (pinfunction "2_2") (pintype "passive"))
    )
    (net (code "86") (name "Net-(IC5-VIN)") (class "Default")
      (node (ref "C3") (pin "+") (pinfunction "+_+") (pintype "passive"))
      (node (ref "IC5") (pin "3") (pinfunction "VIN_3") (pintype "bidirectional"))
      (node (ref "PWR") (pin "2") (pinfunction "2_2") (pintype "passive"))
    )
    (net (code "87") (name "Net-(LED1-PadA)") (class "Default")
      (node (ref "LED1") (pin "A") (pinfunction "A_A") (pintype "passive"))
      (node (ref "R5") (pin "2") (pinfunction "2_2") (pintype "passive"))
    )
    (net (code "88") (name "Net-(OUT-Pad1)") (class "Default")
      (node (ref "OUT") (pin "1") (pinfunction "1_1") (pintype "passive"))
      (node (ref "VOL") (pin "2") (pinfunction "2_2") (pintype "passive"))
    )
    (net (code "89") (name "Net-(R3-Pad1)") (class "Default")
      (node (ref "R3") (pin "1") (pinfunction "1_1") (pintype "passive"))
      (node (ref "SEQLED") (pin "1") (pinfunction "1_1") (pintype "passive"))
    )
    (net (code "90") (name "Net-(R4-Pad1)") (class "Default")
      (node (ref "R4") (pin "1") (pinfunction "1_1") (pintype "passive"))
      (node (ref "SEQLED") (pin "2") (pinfunction "2_2") (pintype "passive"))
    )
    (net (code "91") (name "Net-(R13-Pad1)") (class "Default")
      (node (ref "R13") (pin "1") (pinfunction "1_1") (pintype "passive"))
      (node (ref "SEQLED") (pin "3") (pinfunction "3_3") (pintype "passive"))
    )
    (net (code "92") (name "Net-(R14-Pad1)") (class "Default")
      (node (ref "R14") (pin "1") (pinfunction "1_1") (pintype "passive"))
      (node (ref "SEQLED") (pin "4") (pinfunction "4_4") (pintype "passive"))
    )
    (net (code "93") (name "Net-(R15-Pad1)") (class "Default")
      (node (ref "R15") (pin "1") (pinfunction "1_1") (pintype "passive"))
      (node (ref "SEQLED") (pin "5") (pinfunction "5_5") (pintype "passive"))
    )
    (net (code "94") (name "Net-(R16-Pad1)") (class "Default")
      (node (ref "R16") (pin "1") (pinfunction "1_1") (pintype "passive"))
      (node (ref "SEQLED") (pin "6") (pinfunction "6_6") (pintype "passive"))
    )
    (net (code "95") (name "Net-(R17-Pad1)") (class "Default")
      (node (ref "R17") (pin "1") (pinfunction "1_1") (pintype "passive"))
      (node (ref "SEQLED") (pin "7") (pinfunction "7_7") (pintype "passive"))
    )
    (net (code "96") (name "Net-(R18-Pad1)") (class "Default")
      (node (ref "R18") (pin "1") (pinfunction "1_1") (pintype "passive"))
      (node (ref "SEQLED") (pin "8") (pinfunction "8_8") (pintype "passive"))
    )
    (net (code "97") (name "Net-(R19-Pad1)") (class "Default")
      (node (ref "R19") (pin "1") (pinfunction "1_1") (pintype "passive"))
      (node (ref "SEQLED") (pin "9") (pinfunction "9_9") (pintype "passive"))
    )
    (net (code "98") (name "Net-(R20-Pad1)") (class "Default")
      (node (ref "R20") (pin "1") (pinfunction "1_1") (pintype "passive"))
      (node (ref "SEQLED") (pin "10") (pinfunction "10_10") (pintype "passive"))
    )
    (net (code "99") (name "Net-(R21-Pad1)") (class "Default")
      (node (ref "R21") (pin "1") (pinfunction "1_1") (pintype "passive"))
      (node (ref "SEQLED") (pin "11") (pinfunction "11_11") (pintype "passive"))
    )
    (net (code "100") (name "VCC") (class "Default")
      (node (ref "C1") (pin "1") (pinfunction "1_1") (pintype "passive"))
      (node (ref "C13") (pin "1") (pinfunction "1_1") (pintype "passive"))
      (node (ref "C14") (pin "+") (pinfunction "+_+") (pintype "passive"))
      (node (ref "C17") (pin "1") (pinfunction "1_1") (pintype "passive"))
      (node (ref "C18") (pin "1") (pinfunction "1_1") (pintype "passive"))
      (node (ref "C2") (pin "+") (pinfunction "+_+") (pintype "passive"))
      (node (ref "C4") (pin "1") (pinfunction "1_1") (pintype "passive"))
      (node (ref "C5") (pin "1") (pinfunction "1_1") (pintype "passive"))
      (node (ref "IC1") (pin "10") (pinfunction "VCC_10") (pintype "power_in"))
      (node (ref "IC1") (pin "30") (pinfunction "AVCC_30") (pintype "power_in"))
      (node (ref "IC1") (pin "32") (pinfunction "AREF_32") (pintype "passive"))
      (node (ref "IC2") (pin "20") (pinfunction "AVCC_20") (pintype "bidirectional"))
      (node (ref "IC2") (pin "7") (pinfunction "VCC_7") (pintype "bidirectional"))
      (node (ref "IC3") (pin "12") (pinfunction "PD_12") (pintype "bidirectional"))
      (node (ref "IC3") (pin "14") (pinfunction "CLR_14") (pintype "bidirectional"))
      (node (ref "IC3") (pin "15") (pinfunction "VDD_15") (pintype "bidirectional"))
      (node (ref "IC3") (pin "16") (pinfunction "REFIN_16") (pintype "bidirectional"))
      (node (ref "IC4") (pin "8") (pinfunction "V+_8") (pintype "power_in"))
      (node (ref "IC5") (pin "2") (pinfunction "VOUT_2") (pintype "bidirectional"))
      (node (ref "IC5") (pin "4") (pinfunction "VOUT_4") (pintype "bidirectional"))
      (node (ref "M328ISP") (pin "2") (pinfunction "VCC_2") (pintype "power_in"))
      (node (ref "M32ISP") (pin "2") (pinfunction "VCC_2") (pintype "power_in"))
      (node (ref "POT1") (pin "1") (pinfunction "1_1") (pintype "passive"))
      (node (ref "POT2") (pin "1") (pinfunction "1_1") (pintype "passive"))
      (node (ref "POT3") (pin "1") (pinfunction "1_1") (pintype "passive"))
      (node (ref "POT4") (pin "1") (pinfunction "1_1") (pintype "passive"))
      (node (ref "POT5") (pin "1") (pinfunction "1_1") (pintype "passive"))
      (node (ref "POT6") (pin "1") (pinfunction "1_1") (pintype "passive"))
      (node (ref "POT7") (pin "1") (pinfunction "1_1") (pintype "passive"))
      (node (ref "POT8") (pin "1") (pinfunction "1_1") (pintype "passive"))
      (node (ref "R1") (pin "1") (pinfunction "1_1") (pintype "passive"))
      (node (ref "R2") (pin "1") (pinfunction "1_1") (pintype "passive"))
      (node (ref "SEQPOT") (pin "1") (pinfunction "1_1") (pintype "passive"))
      (node (ref "SEQSW") (pin "3") (pinfunction "3_3") (pintype "passive"))
    )
    (net (code "101") (name "unconnected-(IC2-(PCI11{slash}ADC3)PC3-Pad26)") (class "Default")
      (node (ref "IC2") (pin "26") (pinfunction "(PCI11/ADC3)PC3_26") (pintype "bidirectional"))
    )
    (net (code "102") (name "unconnected-(IC2-(PCI12{slash}ADC4{slash}SDA)PC4-Pad27)") (class "Default")
      (node (ref "IC2") (pin "27") (pinfunction "(PCI12/ADC4/SDA)PC4_27") (pintype "bidirectional"))
    )
    (net (code "103") (name "unconnected-(IC2-(PCI13{slash}ADC5{slash}SCL)PC5-Pad28)") (class "Default")
      (node (ref "IC2") (pin "28") (pinfunction "(PCI13/ADC5/SCL)PC5_28") (pintype "bidirectional"))
    )
    (net (code "104") (name "unconnected-(IC2-(PCI16{slash}RXD)PD0-Pad2)") (class "Default")
      (node (ref "IC2") (pin "2") (pinfunction "(PCI16/RXD)PD0_2") (pintype "bidirectional"))
    )
    (net (code "105") (name "unconnected-(IC2-(PCI18{slash}INT0)PD2-Pad4)") (class "Default")
      (node (ref "IC2") (pin "4") (pinfunction "(PCI18/INT0)PD2_4") (pintype "bidirectional"))
    )
    (net (code "106") (name "unconnected-(IC2-AREF-Pad21)") (class "Default")
      (node (ref "IC2") (pin "21") (pinfunction "AREF_21") (pintype "bidirectional"))
    )
    (net (code "107") (name "unconnected-(P1-PadRING_SW)") (class "Default")
      (node (ref "P1") (pin "RING_SW") (pinfunction "RING_SW_RING_SW") (pintype "bidirectional"))
    )
  )
)
